# superprobe.net
KiCad netlist of a schematic drawn in EAGLE
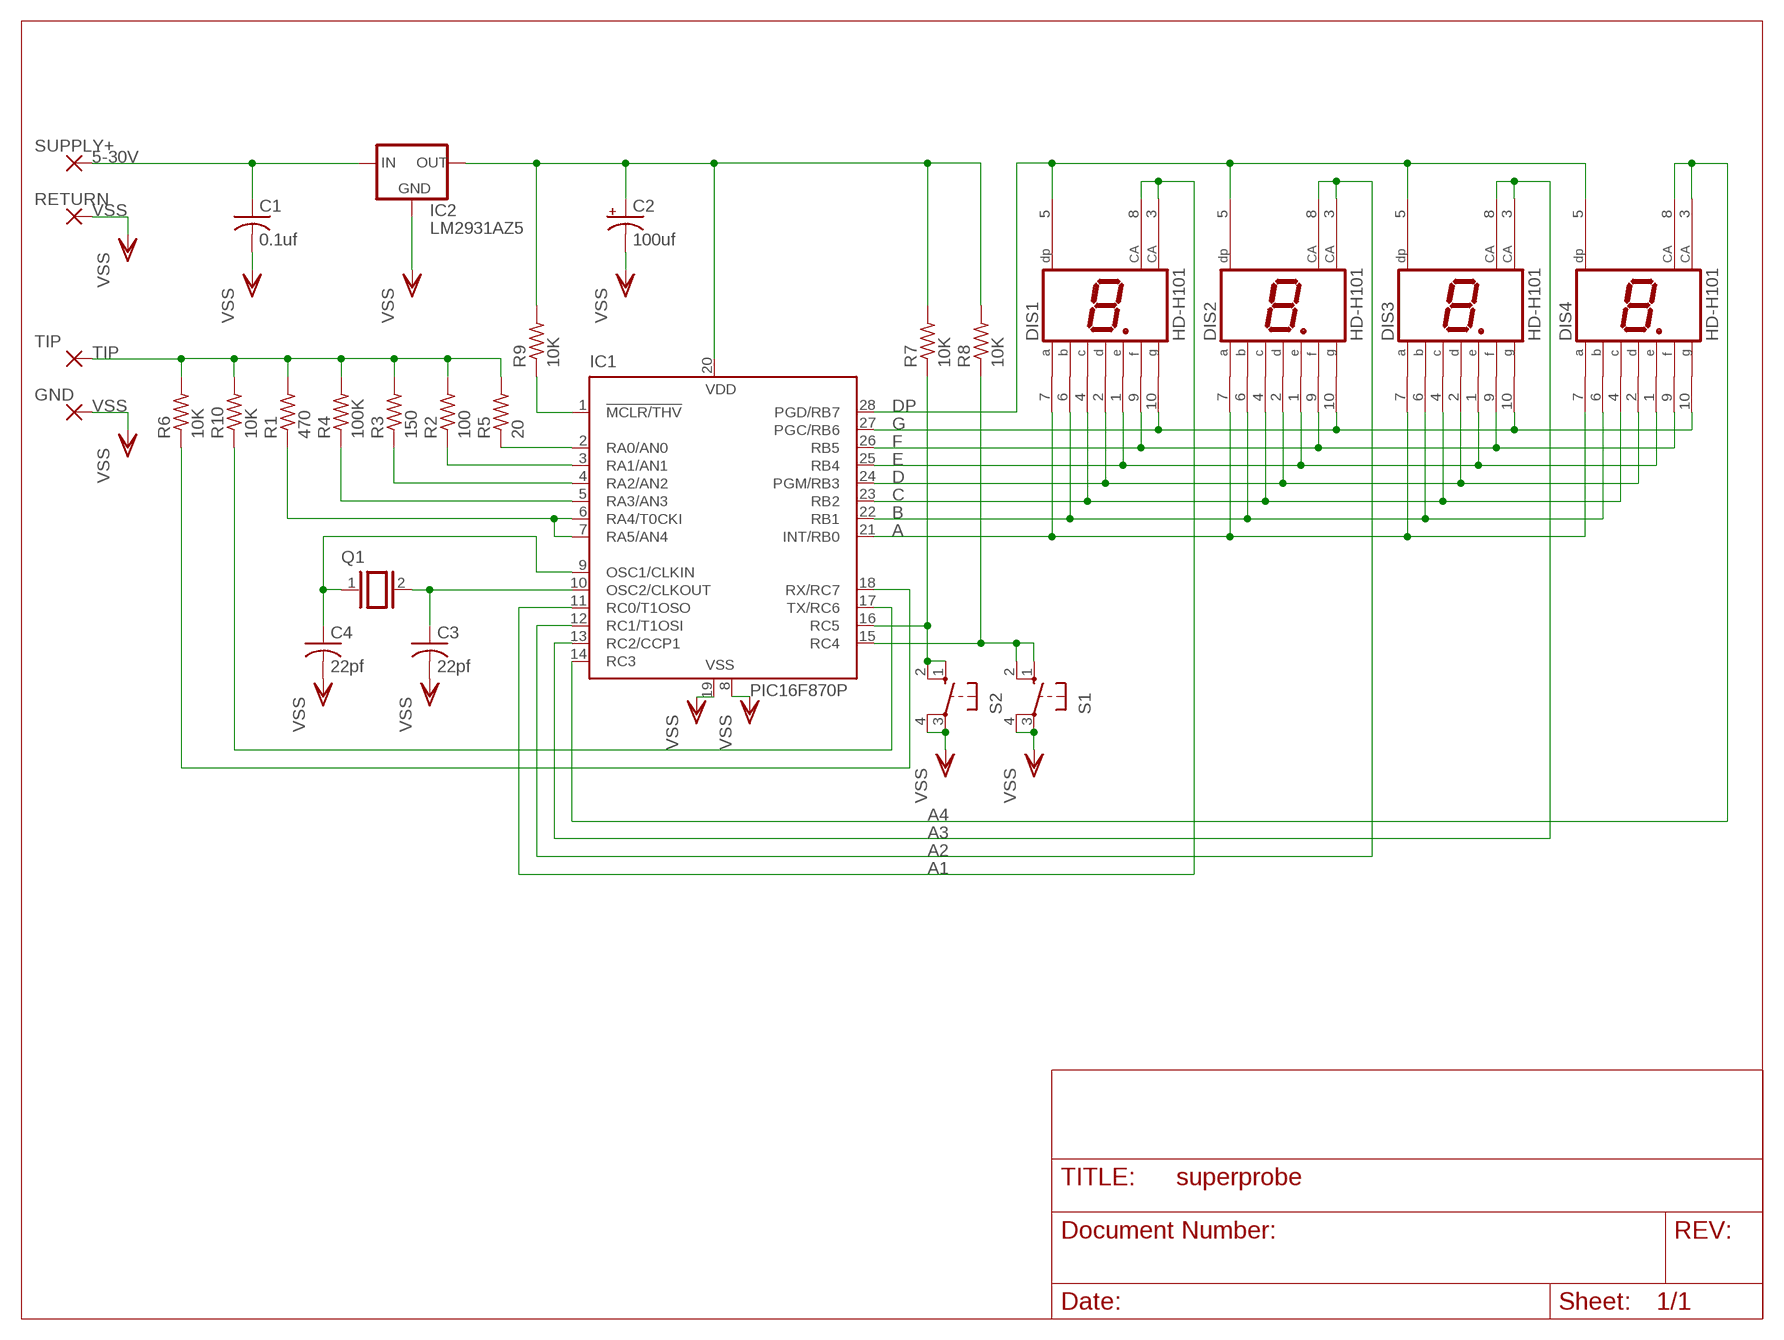
[diagram p0: schematic, sheet 1]

(export (version "E")
  (design (tool "Eeschema 10.0.6"))
  (components
    (comp (ref "C1")
      (value "0.1uf")
      (footprint "eagle-import:C050-025X075")
      (libsource (lib "eagle-import") (part "C-US050-025X075"))
    )
    (comp (ref "C2")
      (value "100uf")
      (footprint "eagle-import:E15-6")
      (libsource (lib "eagle-import") (part "CPOL-USE15-6AXIAL"))
    )
    (comp (ref "C3")
      (value "22pf")
      (footprint "eagle-import:C050-025X075")
      (libsource (lib "eagle-import") (part "C-US050-025X075"))
    )
    (comp (ref "C4")
      (value "22pf")
      (footprint "eagle-import:C050-025X075")
      (libsource (lib "eagle-import") (part "C-US050-025X075"))
    )
    (comp (ref "DIS1")
      (value "HD-H101")
      (footprint "eagle-import:HDSP-M")
      (libsource (lib "eagle-import") (part "HD-H101"))
    )
    (comp (ref "DIS2")
      (value "HD-H101")
      (footprint "eagle-import:HDSP-M")
      (libsource (lib "eagle-import") (part "HD-H101"))
    )
    (comp (ref "DIS3")
      (value "HD-H101")
      (footprint "eagle-import:HDSP-M")
      (libsource (lib "eagle-import") (part "HD-H101"))
    )
    (comp (ref "DIS4")
      (value "HD-H101")
      (footprint "eagle-import:HDSP-M")
      (libsource (lib "eagle-import") (part "HD-H101"))
    )
    (comp (ref "GND")
      (value "PAD-0520")
      (footprint "eagle-import:0520")
      (libsource (lib "eagle-import") (part "PAD-0520"))
    )
    (comp (ref "IC1")
      (value "PIC16F870P")
      (footprint "eagle-import:DIL28-3")
      (fields (field (name "MF") "MICROCHIP") (field (name "MPN") "PIC16F870-I/SP"))
      (libsource (lib "eagle-import") (part "PIC16870PF"))
    )
    (comp (ref "IC2")
      (value "LM2931AZ5")
      (footprint "eagle-import:TO92")
      (libsource (lib "eagle-import") (part "XC63FPL"))
    )
    (comp (ref "Q1")
      (value "XTAL/S")
      (footprint "eagle-import:QS")
      (libsource (lib "eagle-import") (part "XTAL/S"))
    )
    (comp (ref "R1")
      (value "470")
      (footprint "eagle-import:0207_10")
      (libsource (lib "eagle-import") (part "R-US_0207/10"))
    )
    (comp (ref "R2")
      (value "100")
      (footprint "eagle-import:0207_10")
      (libsource (lib "eagle-import") (part "R-US_0207/10"))
    )
    (comp (ref "R3")
      (value "150")
      (footprint "eagle-import:0207_10")
      (libsource (lib "eagle-import") (part "R-US_0207/10"))
    )
    (comp (ref "R4")
      (value "100K")
      (footprint "eagle-import:0207_10")
      (libsource (lib "eagle-import") (part "R-US_0207/10"))
    )
    (comp (ref "R5")
      (value "20")
      (footprint "eagle-import:0207_10")
      (libsource (lib "eagle-import") (part "R-US_0207/10"))
    )
    (comp (ref "R6")
      (value "10K")
      (footprint "eagle-import:0207_10")
      (libsource (lib "eagle-import") (part "R-US_0207/10"))
    )
    (comp (ref "R7")
      (value "10K")
      (footprint "eagle-import:0207_10")
      (libsource (lib "eagle-import") (part "R-US_0207/10"))
    )
    (comp (ref "R8")
      (value "10K")
      (footprint "eagle-import:0207_10")
      (libsource (lib "eagle-import") (part "R-US_0207/10"))
    )
    (comp (ref "R9")
      (value "10K")
      (footprint "eagle-import:0207_10")
      (libsource (lib "eagle-import") (part "R-US_0207/10"))
    )
    (comp (ref "R10")
      (value "10K")
      (footprint "eagle-import:0207_10")
      (libsource (lib "eagle-import") (part "R-US_0207/10"))
    )
    (comp (ref "RETURN")
      (value "PAD-0520")
      (footprint "eagle-import:0520")
      (libsource (lib "eagle-import") (part "PAD-0520"))
    )
    (comp (ref "S1")
      (value "40-XX")
      (footprint "eagle-import:B3F-40XX")
      (fields (field (name "MF") "OMRON COMPONENTS USA") (field (name "MPN") "B3F-4000"))
      (libsource (lib "eagle-import") (part "40-XX"))
    )
    (comp (ref "S2")
      (value "40-XX")
      (footprint "eagle-import:B3F-40XX")
      (fields (field (name "MF") "OMRON COMPONENTS USA") (field (name "MPN") "B3F-4000"))
      (libsource (lib "eagle-import") (part "40-XX"))
    )
    (comp (ref "SUPPLY+")
      (value "PAD-0520")
      (footprint "eagle-import:0520")
      (libsource (lib "eagle-import") (part "PAD-0520"))
    )
    (comp (ref "TIP")
      (value "PAD-0520")
      (footprint "eagle-import:0520")
      (libsource (lib "eagle-import") (part "PAD-0520"))
    )
  )
  (nets
    (net (code "1") (name "/5-30V") (class "Default")
      (node (ref "C1") (pin "1") (pinfunction "1_1") (pintype "passive"))
      (node (ref "IC2") (pin "1") (pinfunction "IN_1") (pintype "input"))
      (node (ref "SUPPLY+") (pin "P$1") (pinfunction "P_P$1") (pintype "passive"))
    )
    (net (code "2") (name "/A") (class "Default")
      (node (ref "DIS1") (pin "7") (pinfunction "A_7") (pintype "passive"))
      (node (ref "DIS2") (pin "7") (pinfunction "A_7") (pintype "passive"))
      (node (ref "DIS3") (pin "7") (pinfunction "A_7") (pintype "passive"))
      (node (ref "DIS4") (pin "7") (pinfunction "A_7") (pintype "passive"))
      (node (ref "IC1") (pin "21") (pinfunction "INT/RB0_21") (pintype "bidirectional"))
    )
    (net (code "3") (name "/A1") (class "Default")
      (node (ref "DIS1") (pin "3") (pinfunction "CA_3") (pintype "passive"))
      (node (ref "DIS1") (pin "8") (pinfunction "CA_8") (pintype "passive"))
      (node (ref "IC1") (pin "11") (pinfunction "RC0/T1OSO_11") (pintype "bidirectional"))
    )
    (net (code "4") (name "/A2") (class "Default")
      (node (ref "DIS2") (pin "3") (pinfunction "CA_3") (pintype "passive"))
      (node (ref "DIS2") (pin "8") (pinfunction "CA_8") (pintype "passive"))
      (node (ref "IC1") (pin "12") (pinfunction "RC1/T1OSI_12") (pintype "bidirectional"))
    )
    (net (code "5") (name "/A3") (class "Default")
      (node (ref "DIS3") (pin "3") (pinfunction "CA_3") (pintype "passive"))
      (node (ref "DIS3") (pin "8") (pinfunction "CA_8") (pintype "passive"))
      (node (ref "IC1") (pin "13") (pinfunction "RC2/CCP1_13") (pintype "bidirectional"))
    )
    (net (code "6") (name "/A4") (class "Default")
      (node (ref "DIS4") (pin "3") (pinfunction "CA_3") (pintype "passive"))
      (node (ref "DIS4") (pin "8") (pinfunction "CA_8") (pintype "passive"))
      (node (ref "IC1") (pin "14") (pinfunction "RC3_14") (pintype "bidirectional"))
    )
    (net (code "7") (name "/B") (class "Default")
      (node (ref "DIS1") (pin "6") (pinfunction "B_6") (pintype "passive"))
      (node (ref "DIS2") (pin "6") (pinfunction "B_6") (pintype "passive"))
      (node (ref "DIS3") (pin "6") (pinfunction "B_6") (pintype "passive"))
      (node (ref "DIS4") (pin "6") (pinfunction "B_6") (pintype "passive"))
      (node (ref "IC1") (pin "22") (pinfunction "RB1_22") (pintype "bidirectional"))
    )
    (net (code "8") (name "/C") (class "Default")
      (node (ref "DIS1") (pin "4") (pinfunction "C_4") (pintype "passive"))
      (node (ref "DIS2") (pin "4") (pinfunction "C_4") (pintype "passive"))
      (node (ref "DIS3") (pin "4") (pinfunction "C_4") (pintype "passive"))
      (node (ref "DIS4") (pin "4") (pinfunction "C_4") (pintype "passive"))
      (node (ref "IC1") (pin "23") (pinfunction "RB2_23") (pintype "bidirectional"))
    )
    (net (code "9") (name "/D") (class "Default")
      (node (ref "DIS1") (pin "2") (pinfunction "D_2") (pintype "passive"))
      (node (ref "DIS2") (pin "2") (pinfunction "D_2") (pintype "passive"))
      (node (ref "DIS3") (pin "2") (pinfunction "D_2") (pintype "passive"))
      (node (ref "DIS4") (pin "2") (pinfunction "D_2") (pintype "passive"))
      (node (ref "IC1") (pin "24") (pinfunction "PGM/RB3_24") (pintype "bidirectional"))
    )
    (net (code "10") (name "/DP") (class "Default")
      (node (ref "DIS1") (pin "5") (pinfunction "DP_5") (pintype "passive"))
      (node (ref "DIS2") (pin "5") (pinfunction "DP_5") (pintype "passive"))
      (node (ref "DIS3") (pin "5") (pinfunction "DP_5") (pintype "passive"))
      (node (ref "DIS4") (pin "5") (pinfunction "DP_5") (pintype "passive"))
      (node (ref "IC1") (pin "28") (pinfunction "PGD/RB7_28") (pintype "bidirectional"))
    )
    (net (code "11") (name "/E") (class "Default")
      (node (ref "DIS1") (pin "1") (pinfunction "E_1") (pintype "passive"))
      (node (ref "DIS2") (pin "1") (pinfunction "E_1") (pintype "passive"))
      (node (ref "DIS3") (pin "1") (pinfunction "E_1") (pintype "passive"))
      (node (ref "DIS4") (pin "1") (pinfunction "E_1") (pintype "passive"))
      (node (ref "IC1") (pin "25") (pinfunction "RB4_25") (pintype "bidirectional"))
    )
    (net (code "12") (name "/F") (class "Default")
      (node (ref "DIS1") (pin "9") (pinfunction "F_9") (pintype "passive"))
      (node (ref "DIS2") (pin "9") (pinfunction "F_9") (pintype "passive"))
      (node (ref "DIS3") (pin "9") (pinfunction "F_9") (pintype "passive"))
      (node (ref "DIS4") (pin "9") (pinfunction "F_9") (pintype "passive"))
      (node (ref "IC1") (pin "26") (pinfunction "RB5_26") (pintype "bidirectional"))
    )
    (net (code "13") (name "/G") (class "Default")
      (node (ref "DIS1") (pin "10") (pinfunction "G_10") (pintype "passive"))
      (node (ref "DIS2") (pin "10") (pinfunction "G_10") (pintype "passive"))
      (node (ref "DIS3") (pin "10") (pinfunction "G_10") (pintype "passive"))
      (node (ref "DIS4") (pin "10") (pinfunction "G_10") (pintype "passive"))
      (node (ref "IC1") (pin "27") (pinfunction "PGC/RB6_27") (pintype "bidirectional"))
    )
    (net (code "14") (name "/TIP") (class "Default")
      (node (ref "R1") (pin "2") (pinfunction "2_2") (pintype "passive"))
      (node (ref "R10") (pin "2") (pinfunction "2_2") (pintype "passive"))
      (node (ref "R2") (pin "2") (pinfunction "2_2") (pintype "passive"))
      (node (ref "R3") (pin "2") (pinfunction "2_2") (pintype "passive"))
      (node (ref "R4") (pin "2") (pinfunction "2_2") (pintype "passive"))
      (node (ref "R5") (pin "2") (pinfunction "2_2") (pintype "passive"))
      (node (ref "R6") (pin "2") (pinfunction "2_2") (pintype "passive"))
      (node (ref "TIP") (pin "P$1") (pinfunction "P_P$1") (pintype "passive"))
    )
    (net (code "15") (name "Net-(IC1-OSC1{slash}CLKIN)") (class "Default")
      (node (ref "C4") (pin "1") (pinfunction "1_1") (pintype "passive"))
      (node (ref "IC1") (pin "9") (pinfunction "OSC1/CLKIN_9") (pintype "input"))
      (node (ref "Q1") (pin "1") (pinfunction "1_1") (pintype "passive"))
    )
    (net (code "16") (name "Net-(IC1-OSC2{slash}CLKOUT)") (class "Default")
      (node (ref "C3") (pin "1") (pinfunction "1_1") (pintype "passive"))
      (node (ref "IC1") (pin "10") (pinfunction "OSC2/CLKOUT_10") (pintype "output"))
      (node (ref "Q1") (pin "2") (pinfunction "2_2") (pintype "passive"))
    )
    (net (code "17") (name "Net-(IC1-RA0{slash}AN0)") (class "Default")
      (node (ref "IC1") (pin "2") (pinfunction "RA0/AN0_2") (pintype "bidirectional"))
      (node (ref "R5") (pin "1") (pinfunction "1_1") (pintype "passive"))
    )
    (net (code "18") (name "Net-(IC1-RA1{slash}AN1)") (class "Default")
      (node (ref "IC1") (pin "3") (pinfunction "RA1/AN1_3") (pintype "bidirectional"))
      (node (ref "R2") (pin "1") (pinfunction "1_1") (pintype "passive"))
    )
    (net (code "19") (name "Net-(IC1-RA2{slash}AN2)") (class "Default")
      (node (ref "IC1") (pin "4") (pinfunction "RA2/AN2_4") (pintype "bidirectional"))
      (node (ref "R3") (pin "1") (pinfunction "1_1") (pintype "passive"))
    )
    (net (code "20") (name "Net-(IC1-RA3{slash}AN3)") (class "Default")
      (node (ref "IC1") (pin "5") (pinfunction "RA3/AN3_5") (pintype "bidirectional"))
      (node (ref "R4") (pin "1") (pinfunction "1_1") (pintype "passive"))
    )
    (net (code "21") (name "Net-(IC1-RA4{slash}T0CKI)") (class "Default")
      (node (ref "IC1") (pin "6") (pinfunction "RA4/T0CKI_6") (pintype "bidirectional"))
      (node (ref "IC1") (pin "7") (pinfunction "RA5/AN4_7") (pintype "bidirectional"))
      (node (ref "R1") (pin "1") (pinfunction "1_1") (pintype "passive"))
    )
    (net (code "22") (name "Net-(IC1-RC4)") (class "Default")
      (node (ref "IC1") (pin "15") (pinfunction "RC4_15") (pintype "bidirectional"))
      (node (ref "R8") (pin "1") (pinfunction "1_1") (pintype "passive"))
      (node (ref "S1") (pin "1") (pinfunction "S_1") (pintype "passive"))
      (node (ref "S1") (pin "2") (pinfunction "S1_2") (pintype "passive"))
    )
    (net (code "23") (name "Net-(IC1-RC5)") (class "Default")
      (node (ref "IC1") (pin "16") (pinfunction "RC5_16") (pintype "bidirectional"))
      (node (ref "R7") (pin "1") (pinfunction "1_1") (pintype "passive"))
      (node (ref "S2") (pin "1") (pinfunction "S_1") (pintype "passive"))
      (node (ref "S2") (pin "2") (pinfunction "S1_2") (pintype "passive"))
    )
    (net (code "24") (name "Net-(IC1-RX{slash}RC7)") (class "Default")
      (node (ref "IC1") (pin "18") (pinfunction "RX/RC7_18") (pintype "bidirectional"))
      (node (ref "R6") (pin "1") (pinfunction "1_1") (pintype "passive"))
    )
    (net (code "25") (name "Net-(IC1-TX{slash}RC6)") (class "Default")
      (node (ref "IC1") (pin "17") (pinfunction "TX/RC6_17") (pintype "bidirectional"))
      (node (ref "R10") (pin "1") (pinfunction "1_1") (pintype "passive"))
    )
    (net (code "26") (name "Net-(IC1-VDD)") (class "Default")
      (node (ref "C2") (pin "+") (pinfunction "+_+") (pintype "passive"))
      (node (ref "IC1") (pin "20") (pinfunction "VDD_20") (pintype "power_in"))
      (node (ref "IC2") (pin "3") (pinfunction "OUT_3") (pintype "passive"))
      (node (ref "R7") (pin "2") (pinfunction "2_2") (pintype "passive"))
      (node (ref "R8") (pin "2") (pinfunction "2_2") (pintype "passive"))
      (node (ref "R9") (pin "2") (pinfunction "2_2") (pintype "passive"))
    )
    (net (code "27") (name "Net-(IC1-~{MCLR{slash}THV})") (class "Default")
      (node (ref "IC1") (pin "1") (pinfunction "~{MCLR/THV}_1") (pintype "input"))
      (node (ref "R9") (pin "1") (pinfunction "1_1") (pintype "passive"))
    )
    (net (code "28") (name "VSS") (class "Default")
      (node (ref "C1") (pin "2") (pinfunction "2_2") (pintype "passive"))
      (node (ref "C2") (pin "-") (pinfunction "-_-") (pintype "passive"))
      (node (ref "C3") (pin "2") (pinfunction "2_2") (pintype "passive"))
      (node (ref "C4") (pin "2") (pinfunction "2_2") (pintype "passive"))
      (node (ref "GND") (pin "P$1") (pinfunction "P_P$1") (pintype "passive"))
      (node (ref "IC1") (pin "19") (pinfunction "VSS_19") (pintype "power_in"))
      (node (ref "IC1") (pin "8") (pinfunction "VSS_8") (pintype "power_in"))
      (node (ref "IC2") (pin "2") (pinfunction "GND_2") (pintype "input"))
      (node (ref "RETURN") (pin "P$1") (pinfunction "P_P$1") (pintype "passive"))
      (node (ref "S1") (pin "3") (pinfunction "P_3") (pintype "passive"))
      (node (ref "S1") (pin "4") (pinfunction "P1_4") (pintype "passive"))
      (node (ref "S2") (pin "3") (pinfunction "P_3") (pintype "passive"))
      (node (ref "S2") (pin "4") (pinfunction "P1_4") (pintype "passive"))
    )
  )
)
